# LSM330DLC.net
KiCad netlist of a schematic drawn in EAGLE
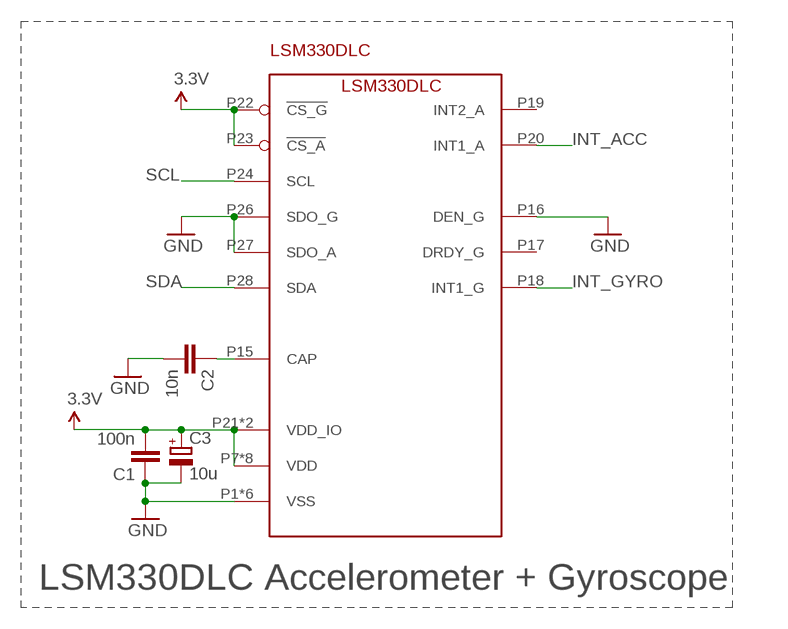
[diagram p0: schematic, sheet 1]

(export (version "E")
  (design (tool "Eeschema 10.0.6"))
  (components
    (comp (ref "C1")
      (value "100n")
      (footprint "eagle-import:C0805")
      (libsource (lib "eagle-import") (part "C-EUC0805"))
    )
    (comp (ref "C2")
      (value "10n")
      (footprint "eagle-import:C0805")
      (libsource (lib "eagle-import") (part "C-EUC0805"))
    )
    (comp (ref "C3")
      (value "10u")
      (footprint "eagle-import:SMC_A")
      (libsource (lib "eagle-import") (part "CPOL-EUSMCA"))
    )
    (comp (ref "LSM330DLC")
      (value "LSM330DLC")
      (footprint "eagle-import:LGA_4X5X1P1_28L")
      (libsource (lib "eagle-import") (part "LSM330DLC"))
    )
  )
  (nets
    (net (code "1") (name "/INT_ACC") (class "Default")
      (node (ref "LSM330DLC") (pin "P20") (pinfunction "INT1_A_P20") (pintype "output"))
    )
    (net (code "2") (name "/INT_GYRO") (class "Default")
      (node (ref "LSM330DLC") (pin "P18") (pinfunction "INT1_G_P18") (pintype "output"))
    )
    (net (code "3") (name "/SCL") (class "Default")
      (node (ref "LSM330DLC") (pin "P24") (pinfunction "SCL_P24") (pintype "input"))
    )
    (net (code "4") (name "/SDA") (class "Default")
      (node (ref "LSM330DLC") (pin "P28") (pinfunction "SDA_P28") (pintype "input"))
    )
    (net (code "5") (name "3.3V") (class "Default")
      (node (ref "C1") (pin "2") (pinfunction "2_2") (pintype "passive"))
      (node (ref "C3") (pin "+") (pinfunction "+_+") (pintype "passive"))
      (node (ref "LSM330DLC") (pin "P10") (pinfunction "VDD_P10") (pintype "power_in"))
      (node (ref "LSM330DLC") (pin "P11") (pinfunction "VDD_P11") (pintype "power_in"))
      (node (ref "LSM330DLC") (pin "P12") (pinfunction "VDD_P12") (pintype "power_in"))
      (node (ref "LSM330DLC") (pin "P13") (pinfunction "VDD_P13") (pintype "power_in"))
      (node (ref "LSM330DLC") (pin "P14") (pinfunction "VDD_P14") (pintype "power_in"))
      (node (ref "LSM330DLC") (pin "P21") (pinfunction "VDD_IO_P21") (pintype "power_in"))
      (node (ref "LSM330DLC") (pin "P22") (pinfunction "~{CS_G}_P22") (pintype "input"))
      (node (ref "LSM330DLC") (pin "P23") (pinfunction "~{CS_A}_P23") (pintype "input"))
      (node (ref "LSM330DLC") (pin "P25") (pinfunction "VDD_IO_P25") (pintype "power_in"))
      (node (ref "LSM330DLC") (pin "P7") (pinfunction "VDD_P7") (pintype "power_in"))
      (node (ref "LSM330DLC") (pin "P8") (pinfunction "VDD_P8") (pintype "power_in"))
      (node (ref "LSM330DLC") (pin "P9") (pinfunction "VDD_P9") (pintype "power_in"))
    )
    (net (code "6") (name "GND") (class "Default")
      (node (ref "C1") (pin "1") (pinfunction "1_1") (pintype "passive"))
      (node (ref "C2") (pin "2") (pinfunction "2_2") (pintype "passive"))
      (node (ref "C3") (pin "-") (pinfunction "-_-") (pintype "passive"))
      (node (ref "LSM330DLC") (pin "P1") (pinfunction "VSS_P1") (pintype "power_in"))
      (node (ref "LSM330DLC") (pin "P16") (pinfunction "DEN_G_P16") (pintype "input"))
      (node (ref "LSM330DLC") (pin "P2") (pinfunction "VSS_P2") (pintype "power_in"))
      (node (ref "LSM330DLC") (pin "P26") (pinfunction "SDO_G_P26") (pintype "output"))
      (node (ref "LSM330DLC") (pin "P27") (pinfunction "SDO_A_P27") (pintype "output"))
      (node (ref "LSM330DLC") (pin "P3") (pinfunction "VSS_P3") (pintype "power_in"))
      (node (ref "LSM330DLC") (pin "P4") (pinfunction "VSS_P4") (pintype "power_in"))
      (node (ref "LSM330DLC") (pin "P5") (pinfunction "VSS_P5") (pintype "power_in"))
      (node (ref "LSM330DLC") (pin "P6") (pinfunction "VSS_P6") (pintype "power_in"))
    )
    (net (code "7") (name "Net-(LSM330DLC-CAP)") (class "Default")
      (node (ref "C2") (pin "1") (pinfunction "1_1") (pintype "passive"))
      (node (ref "LSM330DLC") (pin "P15") (pinfunction "CAP_P15") (pintype "power_in"))
    )
    (net (code "8") (name "unconnected-(LSM330DLC-DRDY_G-PadP17)") (class "Default")
      (node (ref "LSM330DLC") (pin "P17") (pinfunction "DRDY_G_P17") (pintype "output"))
    )
    (net (code "9") (name "unconnected-(LSM330DLC-INT2_A-PadP19)") (class "Default")
      (node (ref "LSM330DLC") (pin "P19") (pinfunction "INT2_A_P19") (pintype "output"))
    )
  )
)
